# USB_Multiplicator_2025.net
KiCad netlist of a schematic drawn in EAGLE
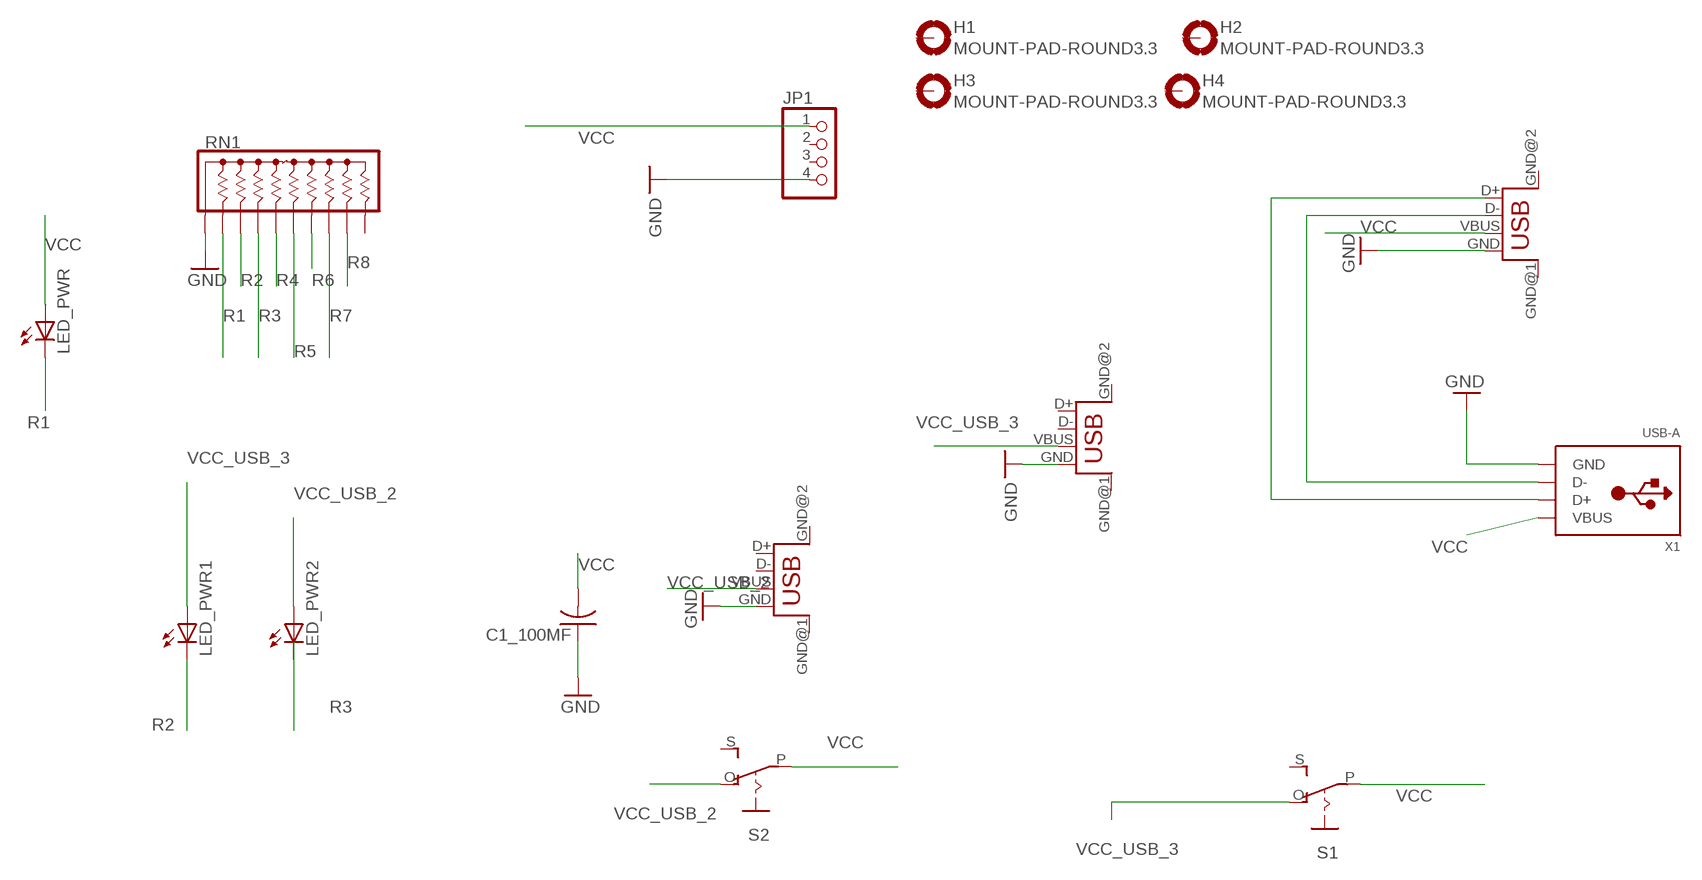
[diagram p0: schematic, sheet 1]

(export (version "E")
  (design (tool "Eeschema 10.0.6"))
  (components
    (comp (ref "C1_100MF")
      (value "C-US025-030X050")
      (footprint "eagle-import:C025-030X050")
      (libsource (lib "eagle-import") (part "C-US025-030X050"))
    )
    (comp (ref "H1")
      (value "MOUNT-PAD-ROUND3.3")
      (footprint "eagle-import:3,3-PAD")
      (libsource (lib "eagle-import") (part "MOUNT-PAD-ROUND3.3"))
    )
    (comp (ref "H2")
      (value "MOUNT-PAD-ROUND3.3")
      (footprint "eagle-import:3,3-PAD")
      (libsource (lib "eagle-import") (part "MOUNT-PAD-ROUND3.3"))
    )
    (comp (ref "H3")
      (value "MOUNT-PAD-ROUND3.3")
      (footprint "eagle-import:3,3-PAD")
      (libsource (lib "eagle-import") (part "MOUNT-PAD-ROUND3.3"))
    )
    (comp (ref "H4")
      (value "MOUNT-PAD-ROUND3.3")
      (footprint "eagle-import:3,3-PAD")
      (libsource (lib "eagle-import") (part "MOUNT-PAD-ROUND3.3"))
    )
    (comp (ref "JP1")
      (value "PINHD-1X4")
      (footprint "eagle-import:1X04")
      (libsource (lib "eagle-import") (part "PINHD-1X4"))
    )
    (comp (ref "LED_PWR")
      (value "LEDSMT1206")
      (footprint "eagle-import:1206")
      (libsource (lib "eagle-import") (part "LEDSMT1206"))
    )
    (comp (ref "LED_PWR1")
      (value "LEDSMT1206")
      (footprint "eagle-import:1206")
      (libsource (lib "eagle-import") (part "LEDSMT1206"))
    )
    (comp (ref "LED_PWR2")
      (value "LEDSMT1206")
      (footprint "eagle-import:1206")
      (libsource (lib "eagle-import") (part "LEDSMT1206"))
    )
    (comp (ref "RN1")
      (value "4610X")
      (footprint "eagle-import:SIP10")
      (libsource (lib "eagle-import") (part "4610X"))
    )
    (comp (ref "S1")
      (value "EG1218S")
      (footprint "eagle-import:EG1218")
      (libsource (lib "eagle-import") (part "EG1218S"))
    )
    (comp (ref "S2")
      (value "EG1218S")
      (footprint "eagle-import:EG1218")
      (libsource (lib "eagle-import") (part "EG1218S"))
    )
    (comp (ref "USB_OUT_1")
      (value "USB")
      (footprint "eagle-import:USB-FEMALE-A-PTH")
      (libsource (lib "eagle-import") (part "USB"))
    )
    (comp (ref "USB_OUT_2")
      (value "USB")
      (footprint "eagle-import:USB-FEMALE-A-PTH")
      (libsource (lib "eagle-import") (part "USB"))
    )
    (comp (ref "USB_OUT_WITH_DATA_1")
      (value "USB")
      (footprint "eagle-import:USB-FEMALE-A-PTH")
      (libsource (lib "eagle-import") (part "USB"))
    )
    (comp (ref "X1")
      (value "USB-A")
      (footprint "eagle-import:MOLEX_480371000")
      (libsource (lib "eagle-import") (part "USB-A"))
    )
  )
  (nets
    (net (code "1") (name "/R1") (class "Default")
      (node (ref "LED_PWR") (pin "C") (pinfunction "C_C") (pintype "passive"))
      (node (ref "RN1") (pin "2") (pinfunction "2_2") (pintype "passive"))
    )
    (net (code "2") (name "/R2") (class "Default")
      (node (ref "LED_PWR1") (pin "C") (pinfunction "C_C") (pintype "passive"))
      (node (ref "RN1") (pin "3") (pinfunction "3_3") (pintype "passive"))
    )
    (net (code "3") (name "/R3") (class "Default")
      (node (ref "LED_PWR2") (pin "C") (pinfunction "C_C") (pintype "passive"))
      (node (ref "RN1") (pin "4") (pinfunction "4_4") (pintype "passive"))
    )
    (net (code "4") (name "/R4") (class "Default")
      (node (ref "RN1") (pin "5") (pinfunction "5_5") (pintype "passive"))
    )
    (net (code "5") (name "/R5") (class "Default")
      (node (ref "RN1") (pin "6") (pinfunction "6_6") (pintype "passive"))
    )
    (net (code "6") (name "/R6") (class "Default")
      (node (ref "RN1") (pin "7") (pinfunction "7_7") (pintype "passive"))
    )
    (net (code "7") (name "/R7") (class "Default")
      (node (ref "RN1") (pin "8") (pinfunction "8_8") (pintype "passive"))
    )
    (net (code "8") (name "/R8") (class "Default")
      (node (ref "RN1") (pin "9") (pinfunction "9_9") (pintype "passive"))
    )
    (net (code "9") (name "/VCC") (class "Default")
      (node (ref "C1_100MF") (pin "2") (pinfunction "2_2") (pintype "passive"))
      (node (ref "JP1") (pin "1") (pinfunction "1_1") (pintype "passive"))
      (node (ref "LED_PWR") (pin "A") (pinfunction "A_A") (pintype "passive"))
      (node (ref "S1") (pin "P") (pinfunction "P_P") (pintype "passive"))
      (node (ref "S2") (pin "P") (pinfunction "P_P") (pintype "passive"))
      (node (ref "USB_OUT_WITH_DATA_1") (pin "VBUS") (pinfunction "VBUS_VBUS") (pintype "bidirectional"))
      (node (ref "X1") (pin "1") (pinfunction "VBUS_1") (pintype "power_in"))
    )
    (net (code "10") (name "/VCC_USB_2") (class "Default")
      (node (ref "LED_PWR2") (pin "A") (pinfunction "A_A") (pintype "passive"))
      (node (ref "S2") (pin "O") (pinfunction "O_O") (pintype "passive"))
      (node (ref "USB_OUT_2") (pin "VBUS") (pinfunction "VBUS_VBUS") (pintype "bidirectional"))
    )
    (net (code "11") (name "/VCC_USB_3") (class "Default")
      (node (ref "LED_PWR1") (pin "A") (pinfunction "A_A") (pintype "passive"))
      (node (ref "S1") (pin "O") (pinfunction "O_O") (pintype "passive"))
      (node (ref "USB_OUT_1") (pin "VBUS") (pinfunction "VBUS_VBUS") (pintype "bidirectional"))
    )
    (net (code "12") (name "GND") (class "Default")
      (node (ref "C1_100MF") (pin "1") (pinfunction "1_1") (pintype "passive"))
      (node (ref "JP1") (pin "4") (pinfunction "4_4") (pintype "passive"))
      (node (ref "RN1") (pin "1") (pinfunction "1_1") (pintype "passive"))
      (node (ref "USB_OUT_1") (pin "GND") (pinfunction "GND_GND") (pintype "bidirectional"))
      (node (ref "USB_OUT_2") (pin "GND") (pinfunction "GND_GND") (pintype "bidirectional"))
      (node (ref "USB_OUT_WITH_DATA_1") (pin "GND") (pinfunction "GND_GND") (pintype "bidirectional"))
      (node (ref "X1") (pin "4") (pinfunction "GND_4") (pintype "power_in"))
    )
    (net (code "13") (name "Net-(X1-D+)") (class "Default")
      (node (ref "USB_OUT_WITH_DATA_1") (pin "D+") (pinfunction "D+_D+") (pintype "bidirectional"))
      (node (ref "X1") (pin "3") (pinfunction "D+_3") (pintype "bidirectional"))
    )
    (net (code "14") (name "Net-(X1-D-)") (class "Default")
      (node (ref "USB_OUT_WITH_DATA_1") (pin "D-") (pinfunction "D-_D-") (pintype "bidirectional"))
      (node (ref "X1") (pin "2") (pinfunction "D-_2") (pintype "bidirectional"))
    )
    (net (code "15") (name "unconnected-(H1-MOUNT-PadB3,3)") (class "Default")
      (node (ref "H1") (pin "B3,3") (pinfunction "MOUNT_B3,3") (pintype "passive"))
    )
    (net (code "16") (name "unconnected-(H2-MOUNT-PadB3,3)") (class "Default")
      (node (ref "H2") (pin "B3,3") (pinfunction "MOUNT_B3,3") (pintype "passive"))
    )
    (net (code "17") (name "unconnected-(H3-MOUNT-PadB3,3)") (class "Default")
      (node (ref "H3") (pin "B3,3") (pinfunction "MOUNT_B3,3") (pintype "passive"))
    )
    (net (code "18") (name "unconnected-(H4-MOUNT-PadB3,3)") (class "Default")
      (node (ref "H4") (pin "B3,3") (pinfunction "MOUNT_B3,3") (pintype "passive"))
    )
    (net (code "19") (name "unconnected-(JP1-Pad2)") (class "Default")
      (node (ref "JP1") (pin "2") (pinfunction "2_2") (pintype "passive"))
    )
    (net (code "20") (name "unconnected-(JP1-Pad3)") (class "Default")
      (node (ref "JP1") (pin "3") (pinfunction "3_3") (pintype "passive"))
    )
    (net (code "21") (name "unconnected-(RN1-Pad10)") (class "Default")
      (node (ref "RN1") (pin "10") (pinfunction "10_10") (pintype "passive"))
    )
    (net (code "22") (name "unconnected-(S1-PadS)") (class "Default")
      (node (ref "S1") (pin "S") (pinfunction "S_S") (pintype "passive"))
    )
    (net (code "23") (name "unconnected-(S2-PadS)") (class "Default")
      (node (ref "S2") (pin "S") (pinfunction "S_S") (pintype "passive"))
    )
    (net (code "24") (name "unconnected-(USB_OUT_1-GND-PadGND@1)") (class "Default")
      (node (ref "USB_OUT_1") (pin "GND@1") (pinfunction "GND_GND@1") (pintype "bidirectional"))
    )
    (net (code "25") (name "unconnected-(USB_OUT_1-GND-PadGND@2)") (class "Default")
      (node (ref "USB_OUT_1") (pin "GND@2") (pinfunction "GND_GND@2") (pintype "bidirectional"))
    )
    (net (code "26") (name "unconnected-(USB_OUT_1-PadD+)") (class "Default")
      (node (ref "USB_OUT_1") (pin "D+") (pinfunction "D+_D+") (pintype "bidirectional"))
    )
    (net (code "27") (name "unconnected-(USB_OUT_1-PadD-)") (class "Default")
      (node (ref "USB_OUT_1") (pin "D-") (pinfunction "D-_D-") (pintype "bidirectional"))
    )
    (net (code "28") (name "unconnected-(USB_OUT_2-GND-PadGND@1)") (class "Default")
      (node (ref "USB_OUT_2") (pin "GND@1") (pinfunction "GND_GND@1") (pintype "bidirectional"))
    )
    (net (code "29") (name "unconnected-(USB_OUT_2-GND-PadGND@2)") (class "Default")
      (node (ref "USB_OUT_2") (pin "GND@2") (pinfunction "GND_GND@2") (pintype "bidirectional"))
    )
    (net (code "30") (name "unconnected-(USB_OUT_2-PadD+)") (class "Default")
      (node (ref "USB_OUT_2") (pin "D+") (pinfunction "D+_D+") (pintype "bidirectional"))
    )
    (net (code "31") (name "unconnected-(USB_OUT_2-PadD-)") (class "Default")
      (node (ref "USB_OUT_2") (pin "D-") (pinfunction "D-_D-") (pintype "bidirectional"))
    )
    (net (code "32") (name "unconnected-(USB_OUT_WITH_DATA_1-GND-PadGND@1)") (class "Default")
      (node (ref "USB_OUT_WITH_DATA_1") (pin "GND@1") (pinfunction "GND_GND@1") (pintype "bidirectional"))
    )
    (net (code "33") (name "unconnected-(USB_OUT_WITH_DATA_1-GND-PadGND@2)") (class "Default")
      (node (ref "USB_OUT_WITH_DATA_1") (pin "GND@2") (pinfunction "GND_GND@2") (pintype "bidirectional"))
    )
  )
)
